# Filtros.net
KiCad netlist of a schematic drawn in Altium Designer
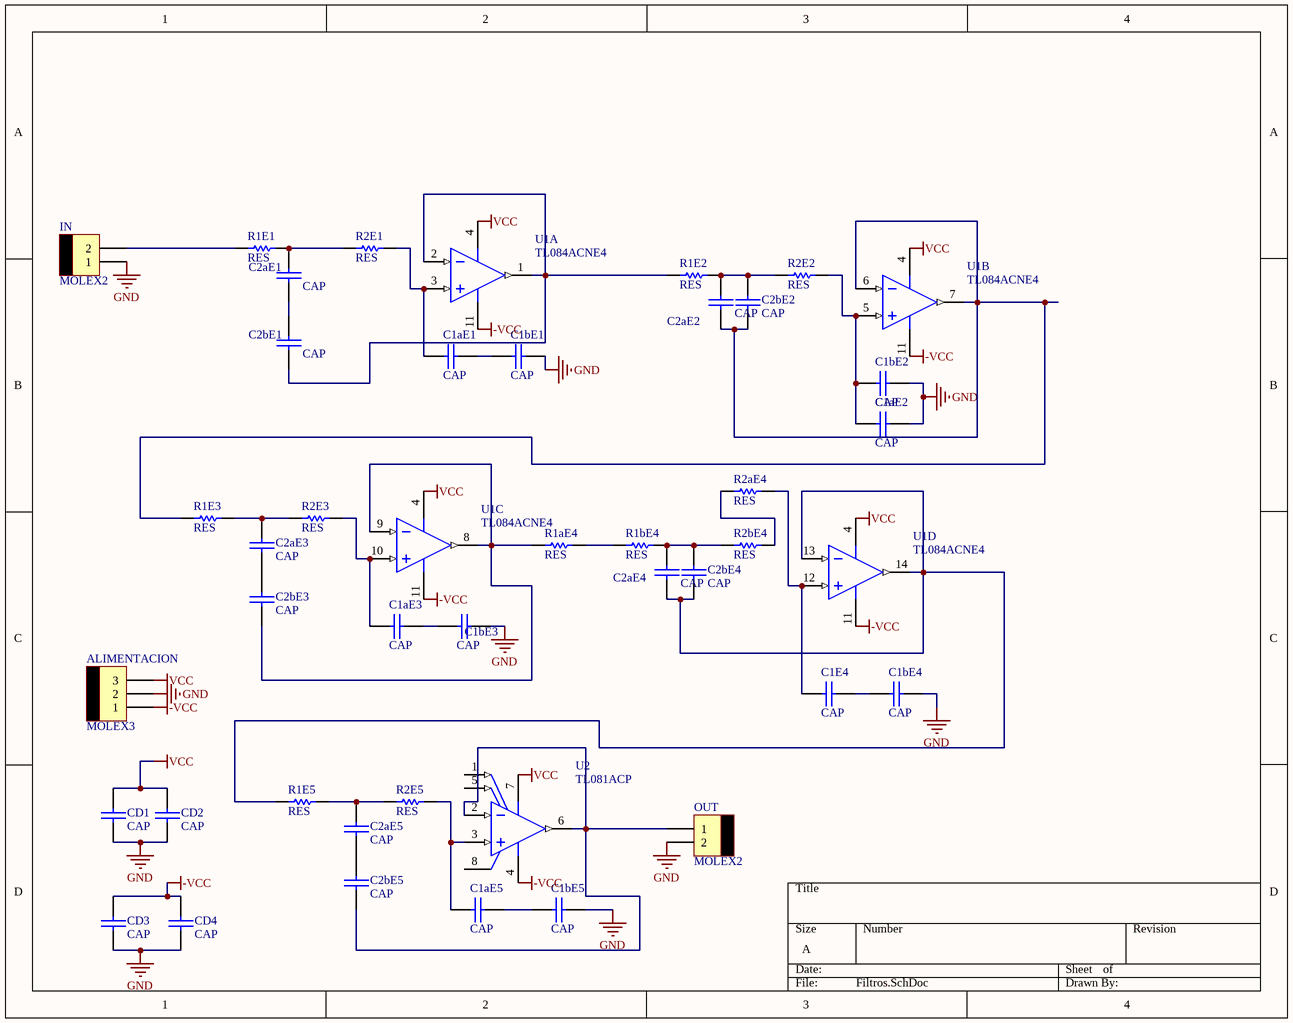
[diagram p0: Filtros.SchDoc]

(export (version "E")
  (design (tool "Eeschema 10.0.6"))
  (components
    (comp (ref "ALIMENTACION")
      (value "MOLEX3")
      (footprint "MOLEX3")
      (libsource (lib "LIB PIO IX") (part "MOLEX3"))
    )
    (comp (ref "C1aE1") (value "CAP") (footprint "0805") (libsource (lib "LIB PIO IX") (part "CAP")))
    (comp (ref "C1aE2") (value "CAP") (footprint "0805") (libsource (lib "LIB PIO IX") (part "CAP")))
    (comp (ref "C1aE3") (value "CAP") (footprint "0805") (libsource (lib "LIB PIO IX") (part "CAP")))
    (comp (ref "C1aE5") (value "CAP") (footprint "0805") (libsource (lib "LIB PIO IX") (part "CAP")))
    (comp (ref "C1bE1") (value "CAP") (footprint "0805") (libsource (lib "LIB PIO IX") (part "CAP")))
    (comp (ref "C1bE2") (value "CAP") (footprint "0805") (libsource (lib "LIB PIO IX") (part "CAP")))
    (comp (ref "C1bE3") (value "CAP") (footprint "0805") (libsource (lib "LIB PIO IX") (part "CAP")))
    (comp (ref "C1bE4") (value "CAP") (footprint "0805") (libsource (lib "LIB PIO IX") (part "CAP")))
    (comp (ref "C1bE5") (value "CAP") (footprint "0805") (libsource (lib "LIB PIO IX") (part "CAP")))
    (comp (ref "C1E4") (value "CAP") (footprint "0805") (libsource (lib "LIB PIO IX") (part "CAP")))
    (comp (ref "C2aE1") (value "CAP") (footprint "0805") (libsource (lib "LIB PIO IX") (part "CAP")))
    (comp (ref "C2aE2") (value "CAP") (footprint "0805") (libsource (lib "LIB PIO IX") (part "CAP")))
    (comp (ref "C2aE3") (value "CAP") (footprint "0805") (libsource (lib "LIB PIO IX") (part "CAP")))
    (comp (ref "C2aE4") (value "CAP") (footprint "0805") (libsource (lib "LIB PIO IX") (part "CAP")))
    (comp (ref "C2aE5") (value "CAP") (footprint "0805") (libsource (lib "LIB PIO IX") (part "CAP")))
    (comp (ref "C2bE1") (value "CAP") (footprint "0805") (libsource (lib "LIB PIO IX") (part "CAP")))
    (comp (ref "C2bE2") (value "CAP") (footprint "0805") (libsource (lib "LIB PIO IX") (part "CAP")))
    (comp (ref "C2bE3") (value "CAP") (footprint "0805") (libsource (lib "LIB PIO IX") (part "CAP")))
    (comp (ref "C2bE4") (value "CAP") (footprint "0805") (libsource (lib "LIB PIO IX") (part "CAP")))
    (comp (ref "C2bE5") (value "CAP") (footprint "0805") (libsource (lib "LIB PIO IX") (part "CAP")))
    (comp (ref "CD1") (value "CAP") (footprint "0805") (libsource (lib "LIB PIO IX") (part "CAP")))
    (comp (ref "CD2") (value "CAP") (footprint "0805") (libsource (lib "LIB PIO IX") (part "CAP")))
    (comp (ref "CD3") (value "CAP") (footprint "0805") (libsource (lib "LIB PIO IX") (part "CAP")))
    (comp (ref "CD4") (value "CAP") (footprint "0805") (libsource (lib "LIB PIO IX") (part "CAP")))
    (comp (ref "IN") (value "MOLEX2") (footprint "MOLEX2") (libsource (lib "") (part "MOLEX2_1")))
    (comp (ref "OUT") (value "MOLEX2") (footprint "MOLEX2") (libsource (lib "LIB PIO IX") (part "MOLEX2")))
    (comp (ref "R1aE4") (value "RES") (footprint "0805") (libsource (lib "LIB PIO IX") (part "RES")))
    (comp (ref "R1bE4") (value "RES") (footprint "0805") (libsource (lib "LIB PIO IX") (part "RES")))
    (comp (ref "R1E1") (value "RES") (footprint "0805") (libsource (lib "LIB PIO IX") (part "RES")))
    (comp (ref "R1E2") (value "RES") (footprint "0805") (libsource (lib "LIB PIO IX") (part "RES")))
    (comp (ref "R1E3") (value "RES") (footprint "0805") (libsource (lib "LIB PIO IX") (part "RES")))
    (comp (ref "R1E5") (value "RES") (footprint "0805") (libsource (lib "LIB PIO IX") (part "RES")))
    (comp (ref "R2aE4") (value "RES") (footprint "0805") (libsource (lib "LIB PIO IX") (part "RES")))
    (comp (ref "R2bE4") (value "RES") (footprint "0805") (libsource (lib "LIB PIO IX") (part "RES")))
    (comp (ref "R2E1") (value "RES") (footprint "0805") (libsource (lib "LIB PIO IX") (part "RES")))
    (comp (ref "R2E2") (value "RES") (footprint "0805") (libsource (lib "LIB PIO IX") (part "RES")))
    (comp (ref "R2E3") (value "RES") (footprint "0805") (libsource (lib "LIB PIO IX") (part "RES")))
    (comp (ref "R2E5") (value "RES") (footprint "0805") (libsource (lib "LIB PIO IX") (part "RES")))
    (comp (ref "U1")
      (value "TL084ACNE4")
      (footprint "TI-N14")
      (description "JFET-Input Operational Amplifier, 7 to 36 V, 0 to 70 degC, 14-pin DIP (N14), Pb-Free (RoHS)")
      (fields (field (name "MANUFACTURER") "Texas Instruments"))
      (libsource (lib "TI Amplifiers and Linear Operational Amplifier General Purpose") (part "TL084ACNE4"))
    )
    (comp (ref "U2")
      (value "TL081ACP")
      (footprint "TI-P8")
      (description "JFET-Input Operational Amplifier, 7 to 36 V, 0 to 70 degC, 8-pin DIP (P8), Pb-Free (RoHS)")
      (fields (field (name "MANUFACTURER") "Texas Instruments"))
      (libsource (lib "TI Amplifiers and Linear Operational Amplifier General Purpose") (part "TL081ACP"))
    )
  )
  (nets
    (net (code "1") (name "-VCC") (class "Default")
      (node (ref "ALIMENTACION") (pin "1") (pinfunction "1_1") (pintype "passive"))
      (node (ref "CD3") (pin "1") (pinfunction "1_1") (pintype "passive"))
      (node (ref "CD4") (pin "1") (pinfunction "1_1") (pintype "passive"))
      (node (ref "U1") (pin "11") (pinfunction "VCC-_11") (pintype "power_in"))
      (node (ref "U2") (pin "4") (pinfunction "VCC-_4") (pintype "power_in"))
    )
    (net (code "2") (name "GND") (class "Default")
      (node (ref "ALIMENTACION") (pin "2") (pinfunction "2_2") (pintype "passive"))
      (node (ref "C1aE2") (pin "2") (pinfunction "2_2") (pintype "passive"))
      (node (ref "C1bE1") (pin "2") (pinfunction "2_2") (pintype "passive"))
      (node (ref "C1bE2") (pin "2") (pinfunction "2_2") (pintype "passive"))
      (node (ref "C1bE3") (pin "2") (pinfunction "2_2") (pintype "passive"))
      (node (ref "C1bE4") (pin "2") (pinfunction "2_2") (pintype "passive"))
      (node (ref "C1bE5") (pin "2") (pinfunction "2_2") (pintype "passive"))
      (node (ref "CD1") (pin "2") (pinfunction "2_2") (pintype "passive"))
      (node (ref "CD2") (pin "2") (pinfunction "2_2") (pintype "passive"))
      (node (ref "CD3") (pin "2") (pinfunction "2_2") (pintype "passive"))
      (node (ref "CD4") (pin "2") (pinfunction "2_2") (pintype "passive"))
      (node (ref "IN") (pin "1") (pinfunction "1_1") (pintype "passive"))
      (node (ref "OUT") (pin "2") (pinfunction "2_2") (pintype "passive"))
    )
    (net (code "3") (name "Net-(C1E4-Pad2)") (class "Default")
      (node (ref "C1E4") (pin "2") (pinfunction "2_2") (pintype "passive"))
      (node (ref "C1bE4") (pin "1") (pinfunction "1_1") (pintype "passive"))
    )
    (net (code "4") (name "Net-(C1aE1-Pad2)") (class "Default")
      (node (ref "C1aE1") (pin "2") (pinfunction "2_2") (pintype "passive"))
      (node (ref "C1bE1") (pin "1") (pinfunction "1_1") (pintype "passive"))
    )
    (net (code "5") (name "Net-(C1aE3-Pad2)") (class "Default")
      (node (ref "C1aE3") (pin "2") (pinfunction "2_2") (pintype "passive"))
      (node (ref "C1bE3") (pin "1") (pinfunction "1_1") (pintype "passive"))
    )
    (net (code "6") (name "Net-(C1aE5-Pad2)") (class "Default")
      (node (ref "C1aE5") (pin "2") (pinfunction "2_2") (pintype "passive"))
      (node (ref "C1bE5") (pin "1") (pinfunction "1_1") (pintype "passive"))
    )
    (net (code "7") (name "Net-(C2aE1-Pad1)") (class "Default")
      (node (ref "C2aE1") (pin "1") (pinfunction "1_1") (pintype "passive"))
      (node (ref "R1E1") (pin "2") (pinfunction "2_2") (pintype "passive"))
      (node (ref "R2E1") (pin "1") (pinfunction "1_1") (pintype "passive"))
    )
    (net (code "8") (name "Net-(C2aE1-Pad2)") (class "Default")
      (node (ref "C2aE1") (pin "2") (pinfunction "2_2") (pintype "passive"))
      (node (ref "C2bE1") (pin "1") (pinfunction "1_1") (pintype "passive"))
    )
    (net (code "9") (name "Net-(C2aE2-Pad1)") (class "Default")
      (node (ref "C2aE2") (pin "1") (pinfunction "1_1") (pintype "passive"))
      (node (ref "C2bE2") (pin "1") (pinfunction "1_1") (pintype "passive"))
      (node (ref "R1E2") (pin "2") (pinfunction "2_2") (pintype "passive"))
      (node (ref "R2E2") (pin "1") (pinfunction "1_1") (pintype "passive"))
    )
    (net (code "10") (name "Net-(C2aE3-Pad1)") (class "Default")
      (node (ref "C2aE3") (pin "1") (pinfunction "1_1") (pintype "passive"))
      (node (ref "R1E3") (pin "2") (pinfunction "2_2") (pintype "passive"))
      (node (ref "R2E3") (pin "1") (pinfunction "1_1") (pintype "passive"))
    )
    (net (code "11") (name "Net-(C2aE3-Pad2)") (class "Default")
      (node (ref "C2aE3") (pin "2") (pinfunction "2_2") (pintype "passive"))
      (node (ref "C2bE3") (pin "1") (pinfunction "1_1") (pintype "passive"))
    )
    (net (code "12") (name "Net-(C2aE4-Pad1)") (class "Default")
      (node (ref "C2aE4") (pin "1") (pinfunction "1_1") (pintype "passive"))
      (node (ref "C2bE4") (pin "1") (pinfunction "1_1") (pintype "passive"))
      (node (ref "R1bE4") (pin "2") (pinfunction "2_2") (pintype "passive"))
      (node (ref "R2bE4") (pin "1") (pinfunction "1_1") (pintype "passive"))
    )
    (net (code "13") (name "Net-(C2aE5-Pad1)") (class "Default")
      (node (ref "C2aE5") (pin "1") (pinfunction "1_1") (pintype "passive"))
      (node (ref "R1E5") (pin "2") (pinfunction "2_2") (pintype "passive"))
      (node (ref "R2E5") (pin "1") (pinfunction "1_1") (pintype "passive"))
    )
    (net (code "14") (name "Net-(C2aE5-Pad2)") (class "Default")
      (node (ref "C2aE5") (pin "2") (pinfunction "2_2") (pintype "passive"))
      (node (ref "C2bE5") (pin "1") (pinfunction "1_1") (pintype "passive"))
    )
    (net (code "15") (name "Net-(IN-Pad2)") (class "Default")
      (node (ref "IN") (pin "2") (pinfunction "2_2") (pintype "passive"))
      (node (ref "R1E1") (pin "1") (pinfunction "1_1") (pintype "passive"))
    )
    (net (code "16") (name "Net-(R1aE4-Pad2)") (class "Default")
      (node (ref "R1aE4") (pin "2") (pinfunction "2_2") (pintype "passive"))
      (node (ref "R1bE4") (pin "1") (pinfunction "1_1") (pintype "passive"))
    )
    (net (code "17") (name "Net-(R2aE4-Pad1)") (class "Default")
      (node (ref "R2aE4") (pin "1") (pinfunction "1_1") (pintype "passive"))
      (node (ref "R2bE4") (pin "2") (pinfunction "2_2") (pintype "passive"))
    )
    (net (code "18") (name "Net-(U1A-IN1+)") (class "Default")
      (node (ref "C1aE1") (pin "1") (pinfunction "1_1") (pintype "passive"))
      (node (ref "R2E1") (pin "2") (pinfunction "2_2") (pintype "passive"))
      (node (ref "U1") (pin "3") (pinfunction "IN1+_3") (pintype "input"))
    )
    (net (code "19") (name "Net-(U1A-IN1-)") (class "Default")
      (node (ref "C2bE1") (pin "2") (pinfunction "2_2") (pintype "passive"))
      (node (ref "R1E2") (pin "1") (pinfunction "1_1") (pintype "passive"))
      (node (ref "U1") (pin "1") (pinfunction "OUT1_1") (pintype "output"))
      (node (ref "U1") (pin "2") (pinfunction "IN1-_2") (pintype "input"))
    )
    (net (code "20") (name "Net-(U1B-IN2+)") (class "Default")
      (node (ref "C1aE2") (pin "1") (pinfunction "1_1") (pintype "passive"))
      (node (ref "C1bE2") (pin "1") (pinfunction "1_1") (pintype "passive"))
      (node (ref "R2E2") (pin "2") (pinfunction "2_2") (pintype "passive"))
      (node (ref "U1") (pin "5") (pinfunction "IN2+_5") (pintype "input"))
    )
    (net (code "21") (name "Net-(U1B-IN2-)") (class "Default")
      (node (ref "C2aE2") (pin "2") (pinfunction "2_2") (pintype "passive"))
      (node (ref "C2bE2") (pin "2") (pinfunction "2_2") (pintype "passive"))
      (node (ref "R1E3") (pin "1") (pinfunction "1_1") (pintype "passive"))
      (node (ref "U1") (pin "6") (pinfunction "IN2-_6") (pintype "input"))
      (node (ref "U1") (pin "7") (pinfunction "OUT2_7") (pintype "output"))
    )
    (net (code "22") (name "Net-(U1C-IN3+)") (class "Default")
      (node (ref "C1aE3") (pin "1") (pinfunction "1_1") (pintype "passive"))
      (node (ref "R2E3") (pin "2") (pinfunction "2_2") (pintype "passive"))
      (node (ref "U1") (pin "10") (pinfunction "IN3+_10") (pintype "input"))
    )
    (net (code "23") (name "Net-(U1C-IN3-)") (class "Default")
      (node (ref "C2bE3") (pin "2") (pinfunction "2_2") (pintype "passive"))
      (node (ref "R1aE4") (pin "1") (pinfunction "1_1") (pintype "passive"))
      (node (ref "U1") (pin "8") (pinfunction "OUT3_8") (pintype "output"))
      (node (ref "U1") (pin "9") (pinfunction "IN3-_9") (pintype "input"))
    )
    (net (code "24") (name "Net-(U1D-IN4+)") (class "Default")
      (node (ref "C1E4") (pin "1") (pinfunction "1_1") (pintype "passive"))
      (node (ref "R2aE4") (pin "2") (pinfunction "2_2") (pintype "passive"))
      (node (ref "U1") (pin "12") (pinfunction "IN4+_12") (pintype "input"))
    )
    (net (code "25") (name "Net-(U1D-IN4-)") (class "Default")
      (node (ref "C2aE4") (pin "2") (pinfunction "2_2") (pintype "passive"))
      (node (ref "C2bE4") (pin "2") (pinfunction "2_2") (pintype "passive"))
      (node (ref "R1E5") (pin "1") (pinfunction "1_1") (pintype "passive"))
      (node (ref "U1") (pin "13") (pinfunction "IN4-_13") (pintype "input"))
      (node (ref "U1") (pin "14") (pinfunction "OUT4_14") (pintype "output"))
    )
    (net (code "26") (name "Net-(U2-IN+)") (class "Default")
      (node (ref "C1aE5") (pin "1") (pinfunction "1_1") (pintype "passive"))
      (node (ref "R2E5") (pin "2") (pinfunction "2_2") (pintype "passive"))
      (node (ref "U2") (pin "3") (pinfunction "IN+_3") (pintype "input"))
    )
    (net (code "27") (name "Net-(U2-IN-)") (class "Default")
      (node (ref "C2bE5") (pin "2") (pinfunction "2_2") (pintype "passive"))
      (node (ref "OUT") (pin "1") (pinfunction "1_1") (pintype "passive"))
      (node (ref "U2") (pin "2") (pinfunction "IN-_2") (pintype "input"))
      (node (ref "U2") (pin "6") (pinfunction "OUT_6") (pintype "output"))
    )
    (net (code "28") (name "VCC") (class "Default")
      (node (ref "ALIMENTACION") (pin "3") (pinfunction "3_3") (pintype "passive"))
      (node (ref "CD1") (pin "1") (pinfunction "1_1") (pintype "passive"))
      (node (ref "CD2") (pin "1") (pinfunction "1_1") (pintype "passive"))
      (node (ref "U1") (pin "4") (pinfunction "VCC+_4") (pintype "power_in"))
      (node (ref "U2") (pin "7") (pinfunction "VCC+_7") (pintype "power_in"))
    )
    (net (code "29") (name "unconnected-(U2-NC-Pad8)") (class "Default")
      (node (ref "U2") (pin "8") (pinfunction "NC_8") (pintype "passive"))
    )
    (net (code "30") (name "unconnected-(U2-OFFSET_N1-Pad1)") (class "Default")
      (node (ref "U2") (pin "1") (pinfunction "OFFSET_N1_1") (pintype "input"))
    )
    (net (code "31") (name "unconnected-(U2-OFFSET_N2-Pad5)") (class "Default")
      (node (ref "U2") (pin "5") (pinfunction "OFFSET_N2_5") (pintype "input"))
    )
  )
)
